# Radio.net
KiCad netlist of a schematic drawn in Altium Designer
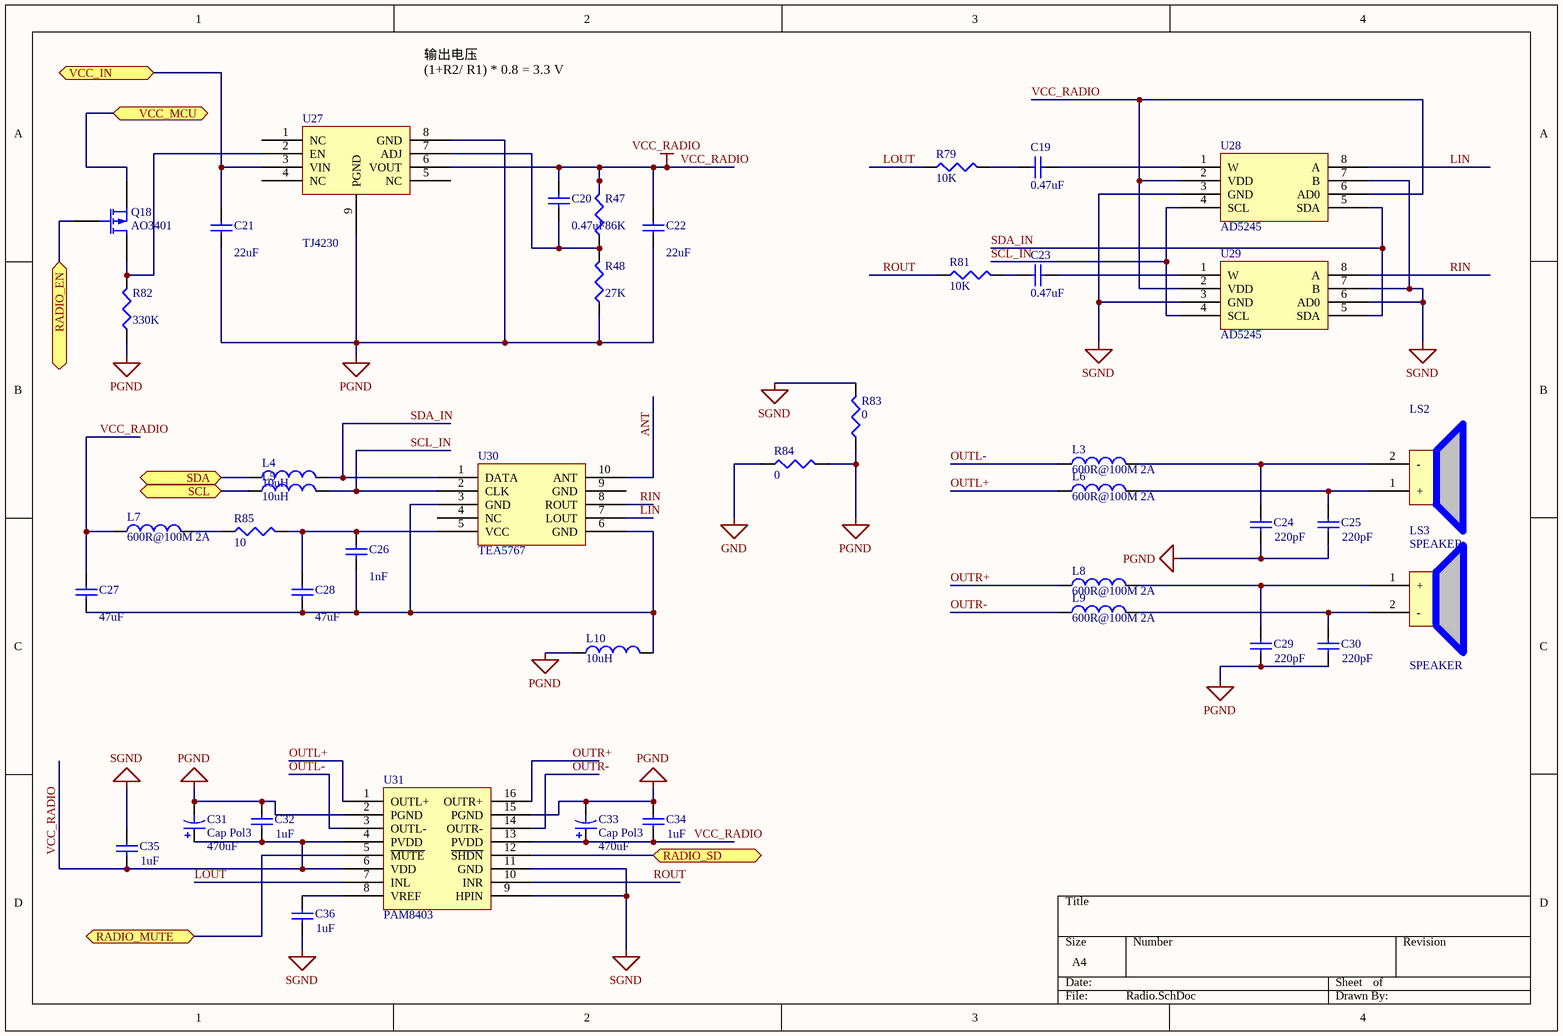
[diagram p0: Radio.SchDoc]

(export (version "E")
  (design (tool "Eeschema 10.0.6"))
  (components
    (comp (ref "C19")
      (value "0.47uF")
      (footprint "clock:0603")
      (description "Capacitor (Semiconductor SIM Model)")
      (fields (field (name "Comment") "Cap Semi") (field (name "PUBLISHER") "Altium Limited"))
      (libsource (lib "Miscellaneous Devices") (part "Cap Semi"))
    )
    (comp (ref "C20")
      (value "0.47uF")
      (footprint "clock:0603")
      (description "Capacitor (Semiconductor SIM Model)")
      (fields (field (name "Comment") "Cap Semi") (field (name "PUBLISHER") "Altium Limited"))
      (libsource (lib "Miscellaneous Devices") (part "Cap Semi"))
    )
    (comp (ref "C21")
      (value "22uF")
      (footprint "clock:1206")
      (description "Capacitor (Semiconductor SIM Model)")
      (fields (field (name "Comment") "Cap Semi") (field (name "PUBLISHER") "Altium Limited"))
      (libsource (lib "Miscellaneous Devices") (part "Cap Semi"))
    )
    (comp (ref "C22")
      (value "22uF")
      (footprint "clock:1206")
      (description "Capacitor (Semiconductor SIM Model)")
      (fields (field (name "Comment") "Cap Semi") (field (name "PUBLISHER") "Altium Limited"))
      (libsource (lib "Miscellaneous Devices") (part "Cap Semi"))
    )
    (comp (ref "C23")
      (value "0.47uF")
      (footprint "clock:0603")
      (description "Capacitor (Semiconductor SIM Model)")
      (fields (field (name "Comment") "Cap Semi") (field (name "PUBLISHER") "Altium Limited"))
      (libsource (lib "Miscellaneous Devices") (part "Cap Semi"))
    )
    (comp (ref "C24")
      (value "220pF")
      (footprint "clock:0603")
      (description "Capacitor (Semiconductor SIM Model)")
      (fields (field (name "Comment") "Cap Semi") (field (name "PUBLISHER") "Altium Limited"))
      (libsource (lib "Miscellaneous Devices") (part "Cap Semi"))
    )
    (comp (ref "C25")
      (value "220pF")
      (footprint "clock:0603")
      (description "Capacitor (Semiconductor SIM Model)")
      (fields (field (name "Comment") "Cap Semi") (field (name "PUBLISHER") "Altium Limited"))
      (libsource (lib "Miscellaneous Devices") (part "Cap Semi"))
    )
    (comp (ref "C26")
      (value "1nF")
      (footprint "clock:0603")
      (description "Capacitor (Semiconductor SIM Model)")
      (fields (field (name "Comment") "Cap Semi") (field (name "PUBLISHER") "Altium Limited"))
      (libsource (lib "Miscellaneous Devices") (part "Cap Semi"))
    )
    (comp (ref "C27")
      (value "47uF")
      (footprint "clock:1210")
      (description "Capacitor (Semiconductor SIM Model)")
      (fields (field (name "Comment") "Cap Semi") (field (name "PUBLISHER") "Altium Limited"))
      (libsource (lib "Miscellaneous Devices") (part "Cap Semi"))
    )
    (comp (ref "C28")
      (value "47uF")
      (footprint "clock:1210")
      (description "Capacitor (Semiconductor SIM Model)")
      (fields (field (name "Comment") "Cap Semi") (field (name "PUBLISHER") "Altium Limited"))
      (libsource (lib "Miscellaneous Devices") (part "Cap Semi"))
    )
    (comp (ref "C29")
      (value "220pF")
      (footprint "clock:0603")
      (description "Capacitor (Semiconductor SIM Model)")
      (fields (field (name "Comment") "Cap Semi") (field (name "PUBLISHER") "Altium Limited"))
      (libsource (lib "Miscellaneous Devices") (part "Cap Semi"))
    )
    (comp (ref "C30")
      (value "220pF")
      (footprint "clock:0603")
      (description "Capacitor (Semiconductor SIM Model)")
      (fields (field (name "Comment") "Cap Semi") (field (name "PUBLISHER") "Altium Limited"))
      (libsource (lib "Miscellaneous Devices") (part "Cap Semi"))
    )
    (comp (ref "C31")
      (value "Cap Pol3")
      (footprint "clock:TC7343-2917")
      (description "Polarized Capacitor (Surface Mount)")
      (fields (field (name "ALTIUM_VALUE") "470uF") (field (name "PUBLISHER") "Altium Limited"))
      (libsource (lib "Miscellaneous Devices") (part "Cap Pol3"))
    )
    (comp (ref "C32")
      (value "1uF")
      (footprint "clock:0603")
      (description "Capacitor (Semiconductor SIM Model)")
      (fields (field (name "Comment") "Cap Semi") (field (name "PUBLISHER") "Altium Limited"))
      (libsource (lib "Miscellaneous Devices") (part "Cap Semi"))
    )
    (comp (ref "C33")
      (value "Cap Pol3")
      (footprint "clock:TC7343-2917")
      (description "Polarized Capacitor (Surface Mount)")
      (fields (field (name "ALTIUM_VALUE") "470uF") (field (name "PUBLISHER") "Altium Limited"))
      (libsource (lib "Miscellaneous Devices") (part "Cap Pol3"))
    )
    (comp (ref "C34")
      (value "1uF")
      (footprint "clock:0603")
      (description "Capacitor (Semiconductor SIM Model)")
      (fields (field (name "Comment") "Cap Semi") (field (name "PUBLISHER") "Altium Limited"))
      (libsource (lib "Miscellaneous Devices") (part "Cap Semi"))
    )
    (comp (ref "C35")
      (value "1uF")
      (footprint "clock:0603")
      (description "Capacitor (Semiconductor SIM Model)")
      (fields (field (name "Comment") "Cap Semi") (field (name "PUBLISHER") "Altium Limited"))
      (libsource (lib "Miscellaneous Devices") (part "Cap Semi"))
    )
    (comp (ref "C36")
      (value "1uF")
      (footprint "clock:0603")
      (description "Capacitor (Semiconductor SIM Model)")
      (fields (field (name "Comment") "Cap Semi") (field (name "PUBLISHER") "Altium Limited"))
      (libsource (lib "Miscellaneous Devices") (part "Cap Semi"))
    )
    (comp (ref "L3")
      (value "600R@100M 2A")
      (footprint "clock:0805")
      (description "Inductor")
      (fields (field (name "PUBLISHER") "Altium Limited"))
      (libsource (lib "Miscellaneous Devices") (part "Inductor"))
    )
    (comp (ref "L4")
      (value "10uH")
      (footprint "clock:0603")
      (description "Inductor")
      (fields (field (name "PUBLISHER") "Altium Limited"))
      (libsource (lib "Miscellaneous Devices") (part "Inductor"))
    )
    (comp (ref "L5")
      (value "10uH")
      (footprint "clock:0603")
      (description "Inductor")
      (fields (field (name "PUBLISHER") "Altium Limited"))
      (libsource (lib "Miscellaneous Devices") (part "Inductor"))
    )
    (comp (ref "L6")
      (value "600R@100M 2A")
      (footprint "clock:0805")
      (description "Inductor")
      (fields (field (name "PUBLISHER") "Altium Limited"))
      (libsource (lib "Miscellaneous Devices") (part "Inductor"))
    )
    (comp (ref "L7")
      (value "600R@100M 2A")
      (footprint "clock:0805")
      (description "Inductor")
      (fields (field (name "PUBLISHER") "Altium Limited"))
      (libsource (lib "Miscellaneous Devices") (part "Inductor"))
    )
    (comp (ref "L8")
      (value "600R@100M 2A")
      (footprint "clock:0805")
      (description "Inductor")
      (fields (field (name "PUBLISHER") "Altium Limited"))
      (libsource (lib "Miscellaneous Devices") (part "Inductor"))
    )
    (comp (ref "L9")
      (value "600R@100M 2A")
      (footprint "clock:0805")
      (description "Inductor")
      (fields (field (name "PUBLISHER") "Altium Limited"))
      (libsource (lib "Miscellaneous Devices") (part "Inductor"))
    )
    (comp (ref "L10")
      (value "10uH")
      (footprint "clock:0603")
      (description "Inductor")
      (fields (field (name "PUBLISHER") "Altium Limited"))
      (libsource (lib "Miscellaneous Devices") (part "Inductor"))
    )
    (comp (ref "LS2")
      (value "SPEAKER")
      (footprint "clock:SPEAKER")
      (libsource (lib "clock") (part "SPEAKER"))
    )
    (comp (ref "LS3") (value "SPEAKER") (footprint "clock:SPEAKER") (libsource (lib "") (part "SPEAKER_1")))
    (comp (ref "Q18")
      (value "AO3401")
      (footprint "clock:SOT23-3-PMOS")
      (description "P-Channel MOSFET")
      (fields (field (name "PUBLISHER") "Altium Limited"))
      (libsource (lib "Miscellaneous Devices") (part "MOSFET-P"))
    )
    (comp (ref "R47")
      (value "86K")
      (footprint "clock:0603")
      (description "Resistor")
      (fields (field (name "Comment") "Res3") (field (name "PUBLISHER") "Altium Limited"))
      (libsource (lib "Miscellaneous Devices") (part "Res3"))
    )
    (comp (ref "R48")
      (value "27K")
      (footprint "clock:0603")
      (description "Resistor")
      (fields (field (name "Comment") "Res3") (field (name "PUBLISHER") "Altium Limited"))
      (libsource (lib "Miscellaneous Devices") (part "Res3"))
    )
    (comp (ref "R79")
      (value "10K")
      (footprint "clock:0603")
      (description "Resistor")
      (fields (field (name "Comment") "Res3") (field (name "PUBLISHER") "Altium Limited"))
      (libsource (lib "Miscellaneous Devices") (part "Res3"))
    )
    (comp (ref "R81")
      (value "10K")
      (footprint "clock:0603")
      (description "Resistor")
      (fields (field (name "Comment") "Res3") (field (name "PUBLISHER") "Altium Limited"))
      (libsource (lib "Miscellaneous Devices") (part "Res3"))
    )
    (comp (ref "R82")
      (value "330K")
      (footprint "clock:0603")
      (description "Resistor")
      (fields (field (name "Comment") "Res3") (field (name "PUBLISHER") "Altium Limited"))
      (libsource (lib "Miscellaneous Devices") (part "Res3"))
    )
    (comp (ref "R83")
      (value "0")
      (footprint "clock:0603")
      (description "Resistor")
      (fields (field (name "Comment") "Res3") (field (name "PUBLISHER") "Altium Limited"))
      (libsource (lib "Miscellaneous Devices") (part "Res3"))
    )
    (comp (ref "R84")
      (value "0")
      (footprint "clock:0603")
      (description "Resistor")
      (fields (field (name "Comment") "Res3") (field (name "PUBLISHER") "Altium Limited"))
      (libsource (lib "Miscellaneous Devices") (part "Res3"))
    )
    (comp (ref "R85")
      (value "10")
      (footprint "clock:0603")
      (description "Resistor")
      (fields (field (name "Comment") "Res3") (field (name "PUBLISHER") "Altium Limited"))
      (libsource (lib "Miscellaneous Devices") (part "Res3"))
    )
    (comp (ref "U27") (value "TJ4230") (footprint "clock:SOP8-PAD") (libsource (lib "clock") (part "TJ4230")))
    (comp (ref "U28") (value "AD5245") (footprint "clock:SOT23-8") (libsource (lib "clock") (part "AD5245")))
    (comp (ref "U29") (value "AD5245") (footprint "clock:SOT23-8") (libsource (lib "clock") (part "AD5245")))
    (comp (ref "U30")
      (value "TEA5767")
      (footprint "clock:TEA5767")
      (libsource (lib "clock") (part "TEA5767"))
    )
    (comp (ref "U31") (value "PAM8403") (footprint "clock:SOP16") (libsource (lib "clock") (part "PAM8403")))
  )
  (nets
    (net (code "1") (name "/ANT") (class "Default")
      (node (ref "U30") (pin "10") (pinfunction "ANT_10") (pintype "passive"))
    )
    (net (code "2") (name "/LIN") (class "Default")
      (node (ref "U28") (pin "8") (pinfunction "A_8") (pintype "passive"))
      (node (ref "U30") (pin "7") (pinfunction "LOUT_7") (pintype "passive"))
    )
    (net (code "3") (name "/LOUT") (class "Default")
      (node (ref "R79") (pin "1") (pinfunction "1_1") (pintype "passive"))
      (node (ref "U31") (pin "7") (pinfunction "INL_7") (pintype "passive"))
    )
    (net (code "4") (name "/OUTL+") (class "Default")
      (node (ref "L6") (pin "1") (pinfunction "1_1") (pintype "passive"))
      (node (ref "U31") (pin "1") (pinfunction "OUTL+_1") (pintype "passive"))
    )
    (net (code "5") (name "/OUTL-") (class "Default")
      (node (ref "L3") (pin "1") (pinfunction "1_1") (pintype "passive"))
      (node (ref "U31") (pin "3") (pinfunction "OUTL-_3") (pintype "passive"))
    )
    (net (code "6") (name "/OUTR+") (class "Default")
      (node (ref "L8") (pin "1") (pinfunction "1_1") (pintype "passive"))
      (node (ref "U31") (pin "16") (pinfunction "OUTR+_16") (pintype "passive"))
    )
    (net (code "7") (name "/OUTR-") (class "Default")
      (node (ref "L9") (pin "1") (pinfunction "1_1") (pintype "passive"))
      (node (ref "U31") (pin "14") (pinfunction "OUTR-_14") (pintype "passive"))
    )
    (net (code "8") (name "/RADIO_EN") (class "Default")
      (node (ref "Q18") (pin "2") (pinfunction "G_2") (pintype "passive"))
    )
    (net (code "9") (name "/RADIO_MUTE") (class "Default")
      (node (ref "U31") (pin "5") (pinfunction "~{MUTE}_5") (pintype "passive"))
    )
    (net (code "10") (name "/RADIO_SD") (class "Default")
      (node (ref "U31") (pin "12") (pinfunction "~{SHDN}_12") (pintype "passive"))
    )
    (net (code "11") (name "/RIN") (class "Default")
      (node (ref "U29") (pin "8") (pinfunction "A_8") (pintype "passive"))
      (node (ref "U30") (pin "8") (pinfunction "ROUT_8") (pintype "passive"))
    )
    (net (code "12") (name "/ROUT") (class "Default")
      (node (ref "R81") (pin "1") (pinfunction "1_1") (pintype "passive"))
      (node (ref "U31") (pin "10") (pinfunction "INR_10") (pintype "passive"))
    )
    (net (code "13") (name "/SCL") (class "Default")
      (node (ref "L5") (pin "1") (pinfunction "1_1") (pintype "passive"))
    )
    (net (code "14") (name "/SCL_IN") (class "Default")
      (node (ref "L5") (pin "2") (pinfunction "2_2") (pintype "passive"))
      (node (ref "U28") (pin "4") (pinfunction "SCL_4") (pintype "passive"))
      (node (ref "U29") (pin "4") (pinfunction "SCL_4") (pintype "passive"))
      (node (ref "U30") (pin "2") (pinfunction "CLK_2") (pintype "passive"))
    )
    (net (code "15") (name "/SDA") (class "Default")
      (node (ref "L4") (pin "1") (pinfunction "1_1") (pintype "passive"))
    )
    (net (code "16") (name "/SDA_IN") (class "Default")
      (node (ref "L4") (pin "2") (pinfunction "2_2") (pintype "passive"))
      (node (ref "U28") (pin "5") (pinfunction "SDA_5") (pintype "passive"))
      (node (ref "U29") (pin "5") (pinfunction "SDA_5") (pintype "passive"))
      (node (ref "U30") (pin "1") (pinfunction "DATA_1") (pintype "passive"))
    )
    (net (code "17") (name "/VCC_IN") (class "Default")
      (node (ref "C21") (pin "2") (pinfunction "2_2") (pintype "passive"))
      (node (ref "U27") (pin "3") (pinfunction "VIN_3") (pintype "passive"))
    )
    (net (code "18") (name "/VCC_MCU") (class "Default")
      (node (ref "Q18") (pin "3") (pinfunction "S_3") (pintype "passive"))
    )
    (net (code "19") (name "GND") (class "Default")
      (node (ref "R84") (pin "1") (pinfunction "1_1") (pintype "passive"))
    )
    (net (code "20") (name "Net-(C19-Pad1)") (class "Default")
      (node (ref "C19") (pin "1") (pinfunction "1_1") (pintype "passive"))
      (node (ref "R79") (pin "2") (pinfunction "2_2") (pintype "passive"))
    )
    (net (code "21") (name "Net-(C23-Pad1)") (class "Default")
      (node (ref "C23") (pin "1") (pinfunction "1_1") (pintype "passive"))
      (node (ref "R81") (pin "2") (pinfunction "2_2") (pintype "passive"))
    )
    (net (code "22") (name "Net-(C26-Pad1)") (class "Default")
      (node (ref "C26") (pin "1") (pinfunction "1_1") (pintype "passive"))
      (node (ref "C27") (pin "1") (pinfunction "1_1") (pintype "passive"))
      (node (ref "C28") (pin "1") (pinfunction "1_1") (pintype "passive"))
      (node (ref "L10") (pin "2") (pinfunction "2_2") (pintype "passive"))
      (node (ref "U30") (pin "3") (pinfunction "GND_3") (pintype "passive"))
      (node (ref "U30") (pin "6") (pinfunction "GND_6") (pintype "passive"))
    )
    (net (code "23") (name "Net-(L7-Pad2)") (class "Default")
      (node (ref "L7") (pin "2") (pinfunction "2_2") (pintype "passive"))
      (node (ref "R85") (pin "1") (pinfunction "1_1") (pintype "passive"))
    )
    (net (code "24") (name "Net-(LS2-+)") (class "Default")
      (node (ref "C25") (pin "2") (pinfunction "2_2") (pintype "passive"))
      (node (ref "L6") (pin "2") (pinfunction "2_2") (pintype "passive"))
      (node (ref "LS2") (pin "1") (pinfunction "+_1") (pintype "passive"))
    )
    (net (code "25") (name "Net-(LS2--)") (class "Default")
      (node (ref "C24") (pin "2") (pinfunction "2_2") (pintype "passive"))
      (node (ref "L3") (pin "2") (pinfunction "2_2") (pintype "passive"))
      (node (ref "LS2") (pin "2") (pinfunction "-_2") (pintype "passive"))
    )
    (net (code "26") (name "Net-(LS3-+)") (class "Default")
      (node (ref "C29") (pin "2") (pinfunction "2_2") (pintype "passive"))
      (node (ref "L8") (pin "2") (pinfunction "2_2") (pintype "passive"))
      (node (ref "LS3") (pin "1") (pinfunction "+_1") (pintype "passive"))
    )
    (net (code "27") (name "Net-(LS3--)") (class "Default")
      (node (ref "C30") (pin "2") (pinfunction "2_2") (pintype "passive"))
      (node (ref "L9") (pin "2") (pinfunction "2_2") (pintype "passive"))
      (node (ref "LS3") (pin "2") (pinfunction "-_2") (pintype "passive"))
    )
    (net (code "28") (name "Net-(Q18-D)") (class "Default")
      (node (ref "Q18") (pin "1") (pinfunction "D_1") (pintype "passive"))
      (node (ref "R82") (pin "2") (pinfunction "2_2") (pintype "passive"))
      (node (ref "U27") (pin "2") (pinfunction "EN_2") (pintype "passive"))
    )
    (net (code "29") (name "Net-(U27-ADJ)") (class "Default")
      (node (ref "C20") (pin "1") (pinfunction "1_1") (pintype "passive"))
      (node (ref "R47") (pin "1") (pinfunction "1_1") (pintype "passive"))
      (node (ref "R48") (pin "2") (pinfunction "2_2") (pintype "passive"))
      (node (ref "U27") (pin "7") (pinfunction "ADJ_7") (pintype "passive"))
    )
    (net (code "30") (name "Net-(U28-W)") (class "Default")
      (node (ref "C19") (pin "2") (pinfunction "2_2") (pintype "passive"))
      (node (ref "U28") (pin "1") (pinfunction "W_1") (pintype "passive"))
    )
    (net (code "31") (name "Net-(U29-W)") (class "Default")
      (node (ref "C23") (pin "2") (pinfunction "2_2") (pintype "passive"))
      (node (ref "U29") (pin "1") (pinfunction "W_1") (pintype "passive"))
    )
    (net (code "32") (name "Net-(U30-VCC)") (class "Default")
      (node (ref "C26") (pin "2") (pinfunction "2_2") (pintype "passive"))
      (node (ref "C28") (pin "2") (pinfunction "2_2") (pintype "passive"))
      (node (ref "R85") (pin "2") (pinfunction "2_2") (pintype "passive"))
      (node (ref "U30") (pin "5") (pinfunction "VCC_5") (pintype "passive"))
    )
    (net (code "33") (name "Net-(U31-VREF)") (class "Default")
      (node (ref "C36") (pin "2") (pinfunction "2_2") (pintype "passive"))
      (node (ref "U31") (pin "8") (pinfunction "VREF_8") (pintype "passive"))
    )
    (net (code "34") (name "PGND") (class "Default")
      (node (ref "C21") (pin "1") (pinfunction "1_1") (pintype "passive"))
      (node (ref "C22") (pin "1") (pinfunction "1_1") (pintype "passive"))
      (node (ref "C24") (pin "1") (pinfunction "1_1") (pintype "passive"))
      (node (ref "C25") (pin "1") (pinfunction "1_1") (pintype "passive"))
      (node (ref "C29") (pin "1") (pinfunction "1_1") (pintype "passive"))
      (node (ref "C30") (pin "1") (pinfunction "1_1") (pintype "passive"))
      (node (ref "C31") (pin "2") (pinfunction "2_2") (pintype "passive"))
      (node (ref "C32") (pin "2") (pinfunction "2_2") (pintype "passive"))
      (node (ref "C33") (pin "2") (pinfunction "2_2") (pintype "passive"))
      (node (ref "C34") (pin "2") (pinfunction "2_2") (pintype "passive"))
      (node (ref "L10") (pin "1") (pinfunction "1_1") (pintype "passive"))
      (node (ref "R48") (pin "1") (pinfunction "1_1") (pintype "passive"))
      (node (ref "R82") (pin "1") (pinfunction "1_1") (pintype "passive"))
      (node (ref "R83") (pin "1") (pinfunction "1_1") (pintype "passive"))
      (node (ref "R84") (pin "2") (pinfunction "2_2") (pintype "passive"))
      (node (ref "U27") (pin "8") (pinfunction "GND_8") (pintype "passive"))
      (node (ref "U27") (pin "9") (pinfunction "PGND_9") (pintype "passive"))
      (node (ref "U31") (pin "15") (pinfunction "PGND_15") (pintype "passive"))
      (node (ref "U31") (pin "2") (pinfunction "PGND_2") (pintype "passive"))
    )
    (net (code "35") (name "SGND") (class "Default")
      (node (ref "C35") (pin "2") (pinfunction "2_2") (pintype "passive"))
      (node (ref "C36") (pin "1") (pinfunction "1_1") (pintype "passive"))
      (node (ref "R83") (pin "2") (pinfunction "2_2") (pintype "passive"))
      (node (ref "U28") (pin "3") (pinfunction "GND_3") (pintype "passive"))
      (node (ref "U28") (pin "7") (pinfunction "B_7") (pintype "passive"))
      (node (ref "U29") (pin "3") (pinfunction "GND_3") (pintype "passive"))
      (node (ref "U29") (pin "6") (pinfunction "AD0_6") (pintype "passive"))
      (node (ref "U29") (pin "7") (pinfunction "B_7") (pintype "passive"))
      (node (ref "U31") (pin "11") (pinfunction "GND_11") (pintype "passive"))
      (node (ref "U31") (pin "9") (pinfunction "HPIN_9") (pintype "passive"))
    )
    (net (code "36") (name "VCC_RADIO") (class "Default")
      (node (ref "C20") (pin "2") (pinfunction "2_2") (pintype "passive"))
      (node (ref "C22") (pin "2") (pinfunction "2_2") (pintype "passive"))
      (node (ref "C27") (pin "2") (pinfunction "2_2") (pintype "passive"))
      (node (ref "C31") (pin "1") (pinfunction "1_1") (pintype "passive"))
      (node (ref "C32") (pin "1") (pinfunction "1_1") (pintype "passive"))
      (node (ref "C33") (pin "1") (pinfunction "1_1") (pintype "passive"))
      (node (ref "C34") (pin "1") (pinfunction "1_1") (pintype "passive"))
      (node (ref "C35") (pin "1") (pinfunction "1_1") (pintype "passive"))
      (node (ref "L7") (pin "1") (pinfunction "1_1") (pintype "passive"))
      (node (ref "R47") (pin "2") (pinfunction "2_2") (pintype "passive"))
      (node (ref "U27") (pin "6") (pinfunction "VOUT_6") (pintype "passive"))
      (node (ref "U28") (pin "2") (pinfunction "VDD_2") (pintype "passive"))
      (node (ref "U28") (pin "6") (pinfunction "AD0_6") (pintype "passive"))
      (node (ref "U29") (pin "2") (pinfunction "VDD_2") (pintype "passive"))
      (node (ref "U31") (pin "13") (pinfunction "PVDD_13") (pintype "passive"))
      (node (ref "U31") (pin "4") (pinfunction "PVDD_4") (pintype "passive"))
      (node (ref "U31") (pin "6") (pinfunction "VDD_6") (pintype "passive"))
    )
    (net (code "37") (name "unconnected-(U27-NC-Pad1)") (class "Default")
      (node (ref "U27") (pin "1") (pinfunction "NC_1") (pintype "passive"))
    )
    (net (code "38") (name "unconnected-(U27-NC-Pad4)") (class "Default")
      (node (ref "U27") (pin "4") (pinfunction "NC_4") (pintype "passive"))
    )
    (net (code "39") (name "unconnected-(U27-NC-Pad5)") (class "Default")
      (node (ref "U27") (pin "5") (pinfunction "NC_5") (pintype "passive"))
    )
    (net (code "40") (name "unconnected-(U30-GND-Pad9)") (class "Default")
      (node (ref "U30") (pin "9") (pinfunction "GND_9") (pintype "passive"))
    )
    (net (code "41") (name "unconnected-(U30-NC-Pad4)") (class "Default")
      (node (ref "U30") (pin "4") (pinfunction "NC_4") (pintype "passive"))
    )
  )
)
